# 555.net
KiCad netlist of a schematic drawn in EAGLE
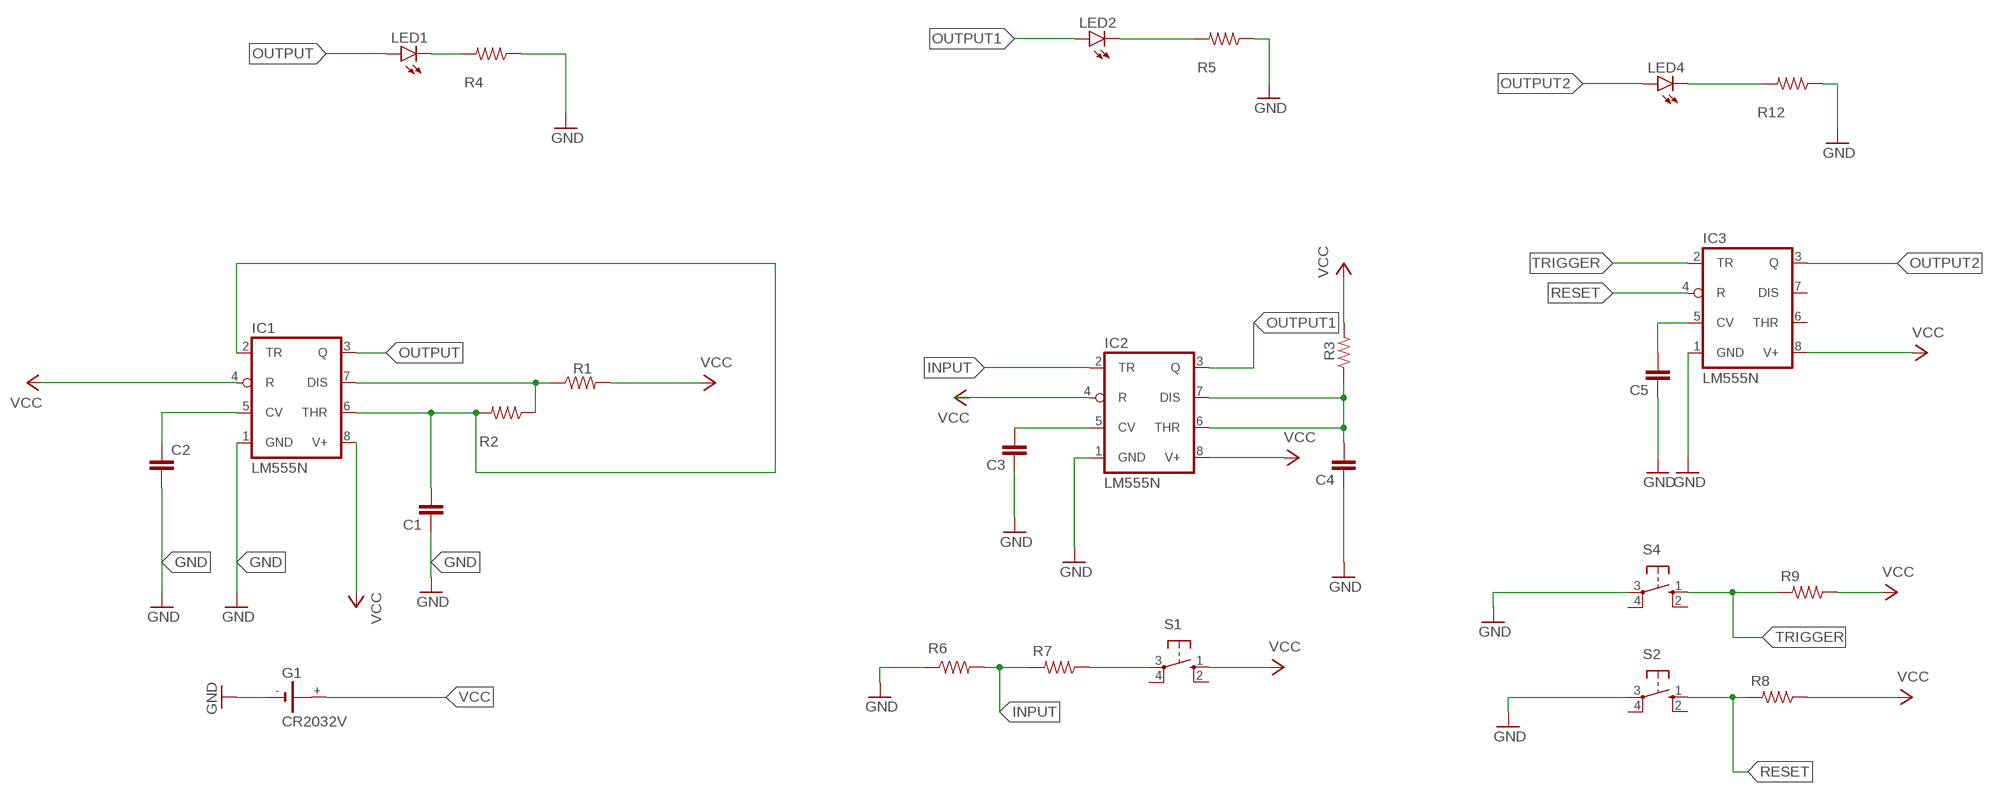
[diagram p0: schematic, sheet 1]

(export (version "E")
  (design (tool "Eeschema 10.0.6"))
  (components
    (comp (ref "C1")
      (value "C-EU025-025X050")
      (footprint "eagle-import:C025-025X050")
      (libsource (lib "eagle-import") (part "C-EU025-025X050"))
    )
    (comp (ref "C2")
      (value "C-EU025-025X050")
      (footprint "eagle-import:C025-025X050")
      (libsource (lib "eagle-import") (part "C-EU025-025X050"))
    )
    (comp (ref "C3")
      (value "C-EU025-025X050")
      (footprint "eagle-import:C025-025X050")
      (libsource (lib "eagle-import") (part "C-EU025-025X050"))
    )
    (comp (ref "C4")
      (value "C-EU025-025X050")
      (footprint "eagle-import:C025-025X050")
      (libsource (lib "eagle-import") (part "C-EU025-025X050"))
    )
    (comp (ref "C5")
      (value "C-EU025-025X050")
      (footprint "eagle-import:C025-025X050")
      (libsource (lib "eagle-import") (part "C-EU025-025X050"))
    )
    (comp (ref "G1")
      (value "CR2032V")
      (footprint "eagle-import:CR2032V")
      (libsource (lib "eagle-import") (part "CR2032V"))
    )
    (comp (ref "IC1")
      (value "LM555N")
      (footprint "eagle-import:DIL08-ROUND")
      (libsource (lib "eagle-import") (part "555NLM"))
    )
    (comp (ref "IC2")
      (value "LM555N")
      (footprint "eagle-import:DIL08-ROUND")
      (libsource (lib "eagle-import") (part "555NLM"))
    )
    (comp (ref "IC3")
      (value "LM555N")
      (footprint "eagle-import:DIL08-ROUND")
      (libsource (lib "eagle-import") (part "555NLM"))
    )
    (comp (ref "LED1")
      (value "LED3MM")
      (footprint "eagle-import:LED3MM")
      (libsource (lib "eagle-import") (part "LED3MM"))
    )
    (comp (ref "LED2")
      (value "LED3MM")
      (footprint "eagle-import:LED3MM")
      (libsource (lib "eagle-import") (part "LED3MM"))
    )
    (comp (ref "LED4")
      (value "LED3MM")
      (footprint "eagle-import:LED3MM")
      (libsource (lib "eagle-import") (part "LED3MM"))
    )
    (comp (ref "R1")
      (value "R-US_R2010")
      (footprint "eagle-import:R2010")
      (libsource (lib "eagle-import") (part "R-US_R2010"))
    )
    (comp (ref "R2")
      (value "R-US_R2010")
      (footprint "eagle-import:R2010")
      (libsource (lib "eagle-import") (part "R-US_R2010"))
    )
    (comp (ref "R3")
      (value "R-US_R2010")
      (footprint "eagle-import:R2010")
      (libsource (lib "eagle-import") (part "R-US_R2010"))
    )
    (comp (ref "R4")
      (value "R-US_R2010")
      (footprint "eagle-import:R2010")
      (libsource (lib "eagle-import") (part "R-US_R2010"))
    )
    (comp (ref "R5")
      (value "R-US_R2010")
      (footprint "eagle-import:R2010")
      (libsource (lib "eagle-import") (part "R-US_R2010"))
    )
    (comp (ref "R6")
      (value "R-US_R2010")
      (footprint "eagle-import:R2010")
      (libsource (lib "eagle-import") (part "R-US_R2010"))
    )
    (comp (ref "R7")
      (value "R-US_R2010")
      (footprint "eagle-import:R2010")
      (libsource (lib "eagle-import") (part "R-US_R2010"))
    )
    (comp (ref "R8")
      (value "R-US_R2010")
      (footprint "eagle-import:R2010")
      (libsource (lib "eagle-import") (part "R-US_R2010"))
    )
    (comp (ref "R9")
      (value "R-US_R2010")
      (footprint "eagle-import:R2010")
      (libsource (lib "eagle-import") (part "R-US_R2010"))
    )
    (comp (ref "R12")
      (value "R-US_R2010")
      (footprint "eagle-import:R2010")
      (libsource (lib "eagle-import") (part "R-US_R2010"))
    )
    (comp (ref "S1")
      (value "10-XX")
      (footprint "eagle-import:B3F-10XX")
      (fields (field (name "MPN") "B3F-1000"))
      (libsource (lib "eagle-import") (part "10-XX"))
    )
    (comp (ref "S2")
      (value "10-XX")
      (footprint "eagle-import:B3F-10XX")
      (fields (field (name "MPN") "B3F-1000"))
      (libsource (lib "eagle-import") (part "10-XX"))
    )
    (comp (ref "S4")
      (value "10-XX")
      (footprint "eagle-import:B3F-10XX")
      (fields (field (name "MPN") "B3F-1000"))
      (libsource (lib "eagle-import") (part "10-XX"))
    )
  )
  (nets
    (net (code "1") (name "GND") (class "Default")
      (node (ref "C1") (pin "1") (pinfunction "1_1") (pintype "passive"))
      (node (ref "C2") (pin "2") (pinfunction "2_2") (pintype "passive"))
      (node (ref "C3") (pin "1") (pinfunction "1_1") (pintype "passive"))
      (node (ref "C4") (pin "1") (pinfunction "1_1") (pintype "passive"))
      (node (ref "C5") (pin "1") (pinfunction "1_1") (pintype "passive"))
      (node (ref "G1") (pin "-") (pinfunction "-_-") (pintype "passive"))
      (node (ref "IC1") (pin "1") (pinfunction "GND_1") (pintype "power_in"))
      (node (ref "IC2") (pin "1") (pinfunction "GND_1") (pintype "power_in"))
      (node (ref "IC3") (pin "1") (pinfunction "GND_1") (pintype "power_in"))
      (node (ref "R12") (pin "1") (pinfunction "1_1") (pintype "passive"))
      (node (ref "R4") (pin "1") (pinfunction "1_1") (pintype "passive"))
      (node (ref "R5") (pin "1") (pinfunction "1_1") (pintype "passive"))
      (node (ref "R6") (pin "1") (pinfunction "1_1") (pintype "passive"))
      (node (ref "S2") (pin "3") (pinfunction "P_3") (pintype "passive"))
      (node (ref "S4") (pin "3") (pinfunction "P_3") (pintype "passive"))
    )
    (net (code "2") (name "INPUT") (class "Default")
      (node (ref "IC2") (pin "2") (pinfunction "TR_2") (pintype "input"))
      (node (ref "R6") (pin "2") (pinfunction "2_2") (pintype "passive"))
      (node (ref "R7") (pin "2") (pinfunction "2_2") (pintype "passive"))
    )
    (net (code "3") (name "Net-(IC1-CV)") (class "Default")
      (node (ref "C2") (pin "1") (pinfunction "1_1") (pintype "passive"))
      (node (ref "IC1") (pin "5") (pinfunction "CV_5") (pintype "input"))
    )
    (net (code "4") (name "Net-(IC1-DIS)") (class "Default")
      (node (ref "IC1") (pin "7") (pinfunction "DIS_7") (pintype "input"))
      (node (ref "R1") (pin "1") (pinfunction "1_1") (pintype "passive"))
      (node (ref "R2") (pin "1") (pinfunction "1_1") (pintype "passive"))
    )
    (net (code "5") (name "Net-(IC1-THR)") (class "Default")
      (node (ref "C1") (pin "2") (pinfunction "2_2") (pintype "passive"))
      (node (ref "IC1") (pin "2") (pinfunction "TR_2") (pintype "input"))
      (node (ref "IC1") (pin "6") (pinfunction "THR_6") (pintype "input"))
      (node (ref "R2") (pin "2") (pinfunction "2_2") (pintype "passive"))
    )
    (net (code "6") (name "Net-(IC2-CV)") (class "Default")
      (node (ref "C3") (pin "2") (pinfunction "2_2") (pintype "passive"))
      (node (ref "IC2") (pin "5") (pinfunction "CV_5") (pintype "input"))
    )
    (net (code "7") (name "Net-(IC2-DIS)") (class "Default")
      (node (ref "C4") (pin "2") (pinfunction "2_2") (pintype "passive"))
      (node (ref "IC2") (pin "6") (pinfunction "THR_6") (pintype "input"))
      (node (ref "IC2") (pin "7") (pinfunction "DIS_7") (pintype "input"))
      (node (ref "R3") (pin "1") (pinfunction "1_1") (pintype "passive"))
    )
    (net (code "8") (name "Net-(IC3-CV)") (class "Default")
      (node (ref "C5") (pin "2") (pinfunction "2_2") (pintype "passive"))
      (node (ref "IC3") (pin "5") (pinfunction "CV_5") (pintype "input"))
    )
    (net (code "9") (name "Net-(LED1-C)") (class "Default")
      (node (ref "LED1") (pin "K") (pinfunction "C_K") (pintype "passive"))
      (node (ref "R4") (pin "2") (pinfunction "2_2") (pintype "passive"))
    )
    (net (code "10") (name "Net-(LED2-C)") (class "Default")
      (node (ref "LED2") (pin "K") (pinfunction "C_K") (pintype "passive"))
      (node (ref "R5") (pin "2") (pinfunction "2_2") (pintype "passive"))
    )
    (net (code "11") (name "Net-(LED4-C)") (class "Default")
      (node (ref "LED4") (pin "K") (pinfunction "C_K") (pintype "passive"))
      (node (ref "R12") (pin "2") (pinfunction "2_2") (pintype "passive"))
    )
    (net (code "12") (name "Net-(S1-P)") (class "Default")
      (node (ref "R7") (pin "1") (pinfunction "1_1") (pintype "passive"))
      (node (ref "S1") (pin "3") (pinfunction "P_3") (pintype "passive"))
    )
    (net (code "13") (name "OUTPUT") (class "Default")
      (node (ref "IC1") (pin "3") (pinfunction "Q_3") (pintype "output"))
      (node (ref "LED1") (pin "A") (pinfunction "A_A") (pintype "passive"))
    )
    (net (code "14") (name "OUTPUT1") (class "Default")
      (node (ref "IC2") (pin "3") (pinfunction "Q_3") (pintype "output"))
      (node (ref "LED2") (pin "A") (pinfunction "A_A") (pintype "passive"))
    )
    (net (code "15") (name "OUTPUT2") (class "Default")
      (node (ref "IC3") (pin "3") (pinfunction "Q_3") (pintype "output"))
      (node (ref "LED4") (pin "A") (pinfunction "A_A") (pintype "passive"))
    )
    (net (code "16") (name "RESET") (class "Default")
      (node (ref "IC3") (pin "4") (pinfunction "R_4") (pintype "input"))
      (node (ref "R8") (pin "2") (pinfunction "2_2") (pintype "passive"))
      (node (ref "S2") (pin "1") (pinfunction "S_1") (pintype "passive"))
    )
    (net (code "17") (name "TRIGGER") (class "Default")
      (node (ref "IC3") (pin "2") (pinfunction "TR_2") (pintype "input"))
      (node (ref "R9") (pin "2") (pinfunction "2_2") (pintype "passive"))
      (node (ref "S4") (pin "1") (pinfunction "S_1") (pintype "passive"))
    )
    (net (code "18") (name "VCC") (class "Default")
      (node (ref "G1") (pin "+") (pinfunction "+_+") (pintype "passive"))
      (node (ref "IC1") (pin "4") (pinfunction "R_4") (pintype "input"))
      (node (ref "IC1") (pin "8") (pinfunction "V+_8") (pintype "power_in"))
      (node (ref "IC2") (pin "4") (pinfunction "R_4") (pintype "input"))
      (node (ref "IC2") (pin "8") (pinfunction "V+_8") (pintype "power_in"))
      (node (ref "IC3") (pin "8") (pinfunction "V+_8") (pintype "power_in"))
      (node (ref "R1") (pin "2") (pinfunction "2_2") (pintype "passive"))
      (node (ref "R3") (pin "2") (pinfunction "2_2") (pintype "passive"))
      (node (ref "R8") (pin "1") (pinfunction "1_1") (pintype "passive"))
      (node (ref "R9") (pin "1") (pinfunction "1_1") (pintype "passive"))
      (node (ref "S1") (pin "1") (pinfunction "S_1") (pintype "passive"))
    )
    (net (code "19") (name "unconnected-(G1-+-Pad+@1)") (class "Default")
      (node (ref "G1") (pin "+@1") (pinfunction "+_+@1") (pintype "passive"))
    )
    (net (code "20") (name "unconnected-(IC3-DIS-Pad7)") (class "Default")
      (node (ref "IC3") (pin "7") (pinfunction "DIS_7") (pintype "input"))
    )
    (net (code "21") (name "unconnected-(IC3-THR-Pad6)") (class "Default")
      (node (ref "IC3") (pin "6") (pinfunction "THR_6") (pintype "input"))
    )
    (net (code "22") (name "unconnected-(S1-P1-Pad4)") (class "Default")
      (node (ref "S1") (pin "4") (pinfunction "P1_4") (pintype "passive"))
    )
    (net (code "23") (name "unconnected-(S1-S1-Pad2)") (class "Default")
      (node (ref "S1") (pin "2") (pinfunction "S1_2") (pintype "passive"))
    )
    (net (code "24") (name "unconnected-(S2-P1-Pad4)") (class "Default")
      (node (ref "S2") (pin "4") (pinfunction "P1_4") (pintype "passive"))
    )
    (net (code "25") (name "unconnected-(S2-S1-Pad2)") (class "Default")
      (node (ref "S2") (pin "2") (pinfunction "S1_2") (pintype "passive"))
    )
    (net (code "26") (name "unconnected-(S4-P1-Pad4)") (class "Default")
      (node (ref "S4") (pin "4") (pinfunction "P1_4") (pintype "passive"))
    )
    (net (code "27") (name "unconnected-(S4-S1-Pad2)") (class "Default")
      (node (ref "S4") (pin "2") (pinfunction "S1_2") (pintype "passive"))
    )
  )
)
